# FPGA_config.net
KiCad netlist of a schematic drawn in Altium Designer
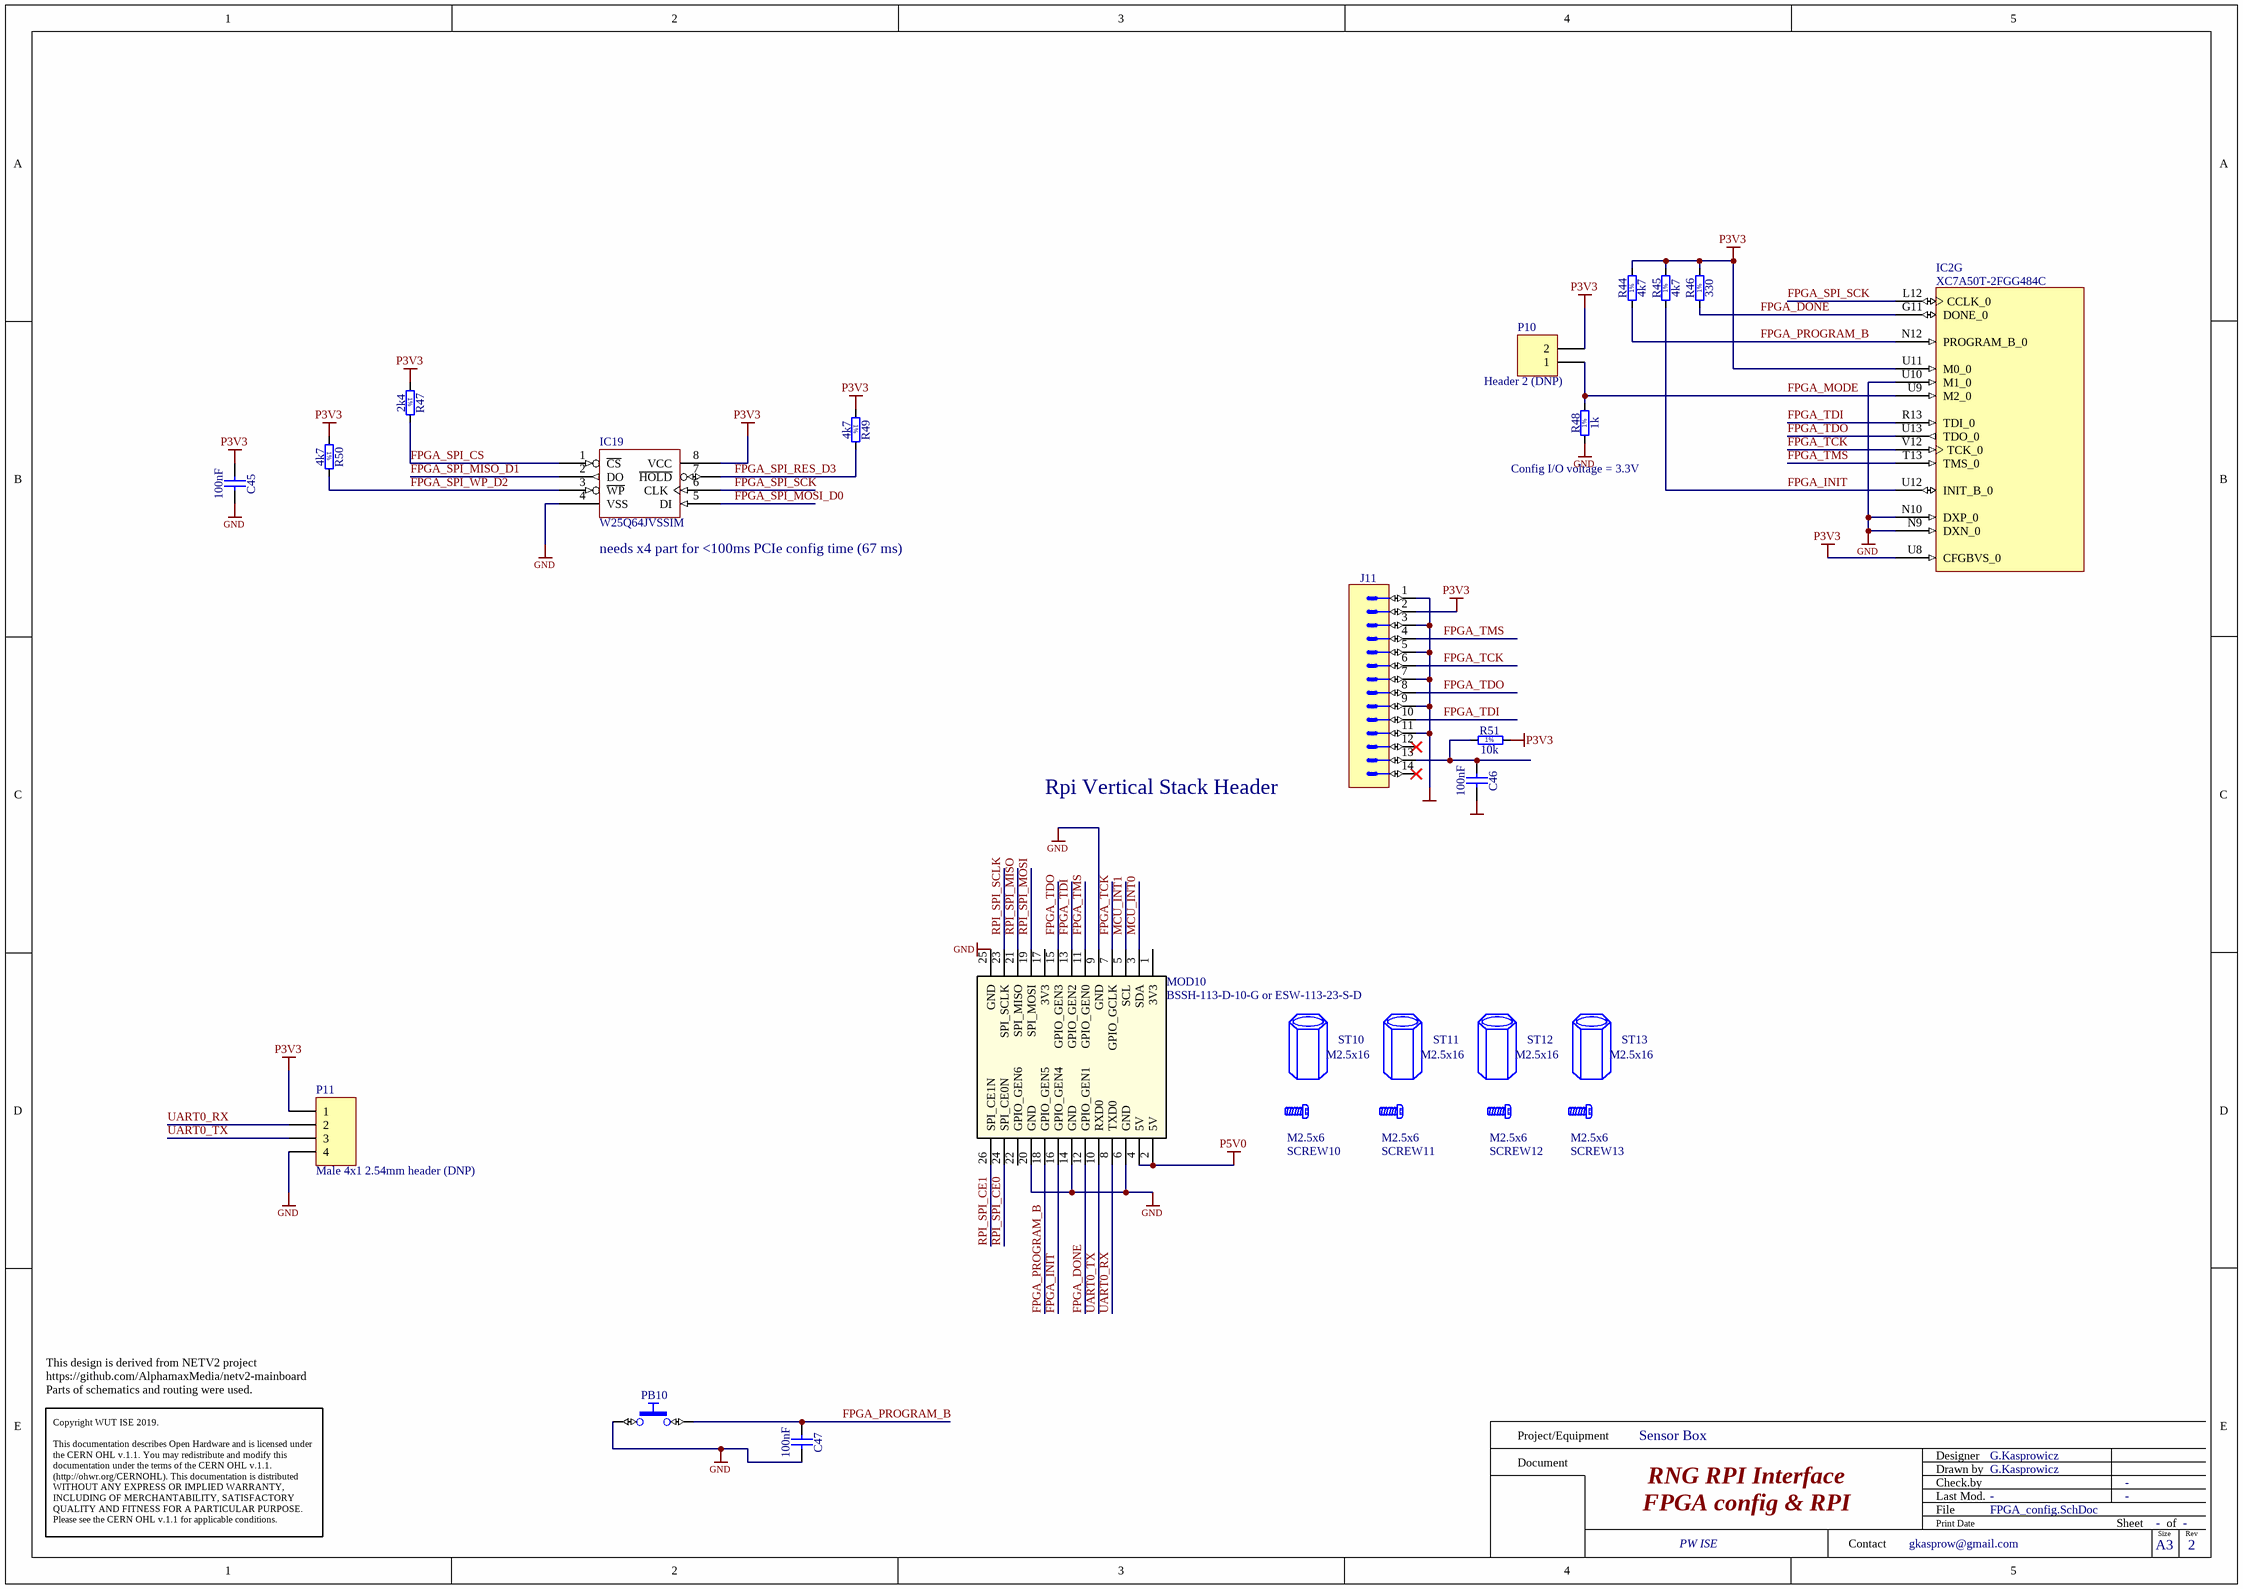
[diagram p0: FPGA_config.SchDoc]

(export (version "E")
  (design (tool "Eeschema 10.0.6"))
  (components
    (comp (ref "C45")
      (value "100nF")
      (footprint "CAPC0603X33N")
      (description "Non-polarised capacitor")
      (fields
        (field (name "PART NUMBER") "CC0201_100NF_6.3V_10%_X5R")
        (field (name "VOLTAGE") "6.3V")
        (field (name "AUTHOR") "CERN DEM JLC")
      )
      (libsource (lib "Capacitors") (part "Capacitor - non polarized"))
    )
    (comp (ref "C46")
      (value "100nF")
      (footprint "CAPC0603X33N")
      (description "Non-polarised capacitor")
      (fields
        (field (name "PART NUMBER") "CC0201_100NF_6.3V_10%_X5R")
        (field (name "VOLTAGE") "6.3V")
        (field (name "AUTHOR") "CERN DEM JLC")
      )
      (libsource (lib "Capacitors") (part "Capacitor - non polarized"))
    )
    (comp (ref "C47")
      (value "100nF")
      (footprint "CAPC0603X33N")
      (description "Non-polarised capacitor")
      (fields
        (field (name "PART NUMBER") "CC0201_100NF_6.3V_10%_X5R")
        (field (name "VOLTAGE") "6.3V")
        (field (name "AUTHOR") "CERN DEM JLC")
      )
      (libsource (lib "Capacitors") (part "Capacitor - non polarized"))
    )
    (comp (ref "IC2")
      (value "XC7A50T-2FGG484C")
      (footprint "BGA484C100P22X22_2300X2300X260")
      (fields (field (name "MANUFACTURER") "XILINX") (field (name "AUTHOR") "CERN DEM JMW"))
      (libsource (lib "ICs And Semiconductors") (part "XC7A50T-2FGG484C"))
    )
    (comp (ref "IC19")
      (value "W25Q64JVSSIM")
      (footprint "SOIC127P790X216-8N")
      (description "64Mbit SPI NOR FLASH")
      (libsource (lib "commonsch") (part "EN25P05-50GCP"))
    )
    (comp (ref "J11")
      (value "Milli-Grid™")
      (footprint "MOLEX_87832-1420")
      (description "Connector 14 Male")
      (fields
        (field (name "PART NUMBER") "MOLEX_87832-1420")
        (field (name "MANUFACTURER") "MOLEX")
        (field (name "AUTHOR") "CERN DEM JLC")
      )
      (libsource (lib "Connectors") (part "Connector 14 Male"))
    )
    (comp (ref "MOD10")
      (value "BSSH-113-D-10-G or ESW-113-23-S-D")
      (footprint "Raspberr Pi - 26")
      (description "Raspberry Pi - 26")
      (fields (field (name "MANUFACTURER") "Major League Electroncis"))
      (libsource (lib "Modules") (part "Raspberry Pi - 26"))
    )
    (comp (ref "P10")
      (value "Header 2 (DNP)")
      (footprint "HDR1X2")
      (description "Header, 2-Pin")
      (fields (field (name "MPN") "DNP") (field (name "PUBLISHER") "Altium Limited"))
      (libsource (lib "Miscellaneous Connectors") (part "Header 2"))
    )
    (comp (ref "P11")
      (value "Male 4x1 2.54mm header (DNP)")
      (footprint "HDR1X4")
      (description "Header, 4-Pin")
      (fields (field (name "MPN") "DNP") (field (name "PUBLISHER") "Altium Limited"))
      (libsource (lib "Miscellaneous Connectors") (part "Header 4"))
    )
    (comp (ref "PB10")
      (value "Push Button")
      (footprint "PB_TYCO_FSMSM")
      (description "Push-Button Switch SPDT")
      (fields
        (field (name "PART NUMBER") "PB_TYCO_FSMSM")
        (field (name "MANUFACTURER") "TYCO ELECTRONICS")
        (field (name "AUTHOR") "CERN DEM JLC")
      )
      (libsource (lib "Eletro-mechanical") (part "PB SPST 1NO-2NO"))
    )
    (comp (ref "R44")
      (value "4k7")
      (footprint "RESC1005X40N")
      (description "Resistor - 1%")
      (fields
        (field (name "PART NUMBER") "R0402_4K7_1%_0.0625W_100PPM")
        (field (name "POWER") "0.0625W")
        (field (name "AUTHOR") "CERN DEM JLC")
      )
      (libsource (lib "Resistors") (part "Resistor - 1%"))
    )
    (comp (ref "R45")
      (value "4k7")
      (footprint "RESC1005X40N")
      (description "Resistor - 1%")
      (fields
        (field (name "PART NUMBER") "R0402_4K7_1%_0.0625W_100PPM")
        (field (name "POWER") "0.0625W")
        (field (name "AUTHOR") "CERN DEM JLC")
      )
      (libsource (lib "Resistors") (part "Resistor - 1%"))
    )
    (comp (ref "R46")
      (value "330")
      (footprint "RESC1005X40N")
      (description "Resistor - 1%")
      (fields
        (field (name "PART NUMBER") "R0402_330R_1%_0.0625W_100PPM")
        (field (name "POWER") "0.0625W")
        (field (name "AUTHOR") "CERN DEM JLC")
      )
      (libsource (lib "Resistors") (part "Resistor - 1%"))
    )
    (comp (ref "R47")
      (value "2k4")
      (footprint "RESC1005X40N")
      (description "Resistor - 1%")
      (fields
        (field (name "PART NUMBER") "R0402_2K4_1%_0.0625W_100PPM")
        (field (name "POWER") "0.0625W")
        (field (name "AUTHOR") "CERN DEM JLC")
      )
      (libsource (lib "Resistors") (part "Resistor - 1%"))
    )
    (comp (ref "R48")
      (value "1k")
      (footprint "RESC1005X40N")
      (description "Resistor - 1%")
      (fields
        (field (name "PART NUMBER") "R0402_1K_1%_0.0625W_100PPM")
        (field (name "POWER") "0.0625W")
        (field (name "AUTHOR") "CERN DEM JLC")
      )
      (libsource (lib "Resistors") (part "Resistor - 1%"))
    )
    (comp (ref "R49")
      (value "4k7")
      (footprint "RESC1005X40N")
      (description "Resistor - 1%")
      (fields
        (field (name "PART NUMBER") "R0402_4K7_1%_0.0625W_100PPM")
        (field (name "POWER") "0.0625W")
        (field (name "AUTHOR") "CERN DEM JLC")
      )
      (libsource (lib "Resistors") (part "Resistor - 1%"))
    )
    (comp (ref "R50")
      (value "4k7")
      (footprint "RESC1005X40N")
      (description "Resistor - 1%")
      (fields
        (field (name "PART NUMBER") "R0402_4K7_1%_0.0625W_100PPM")
        (field (name "POWER") "0.0625W")
        (field (name "AUTHOR") "CERN DEM JLC")
      )
      (libsource (lib "Resistors") (part "Resistor - 1%"))
    )
    (comp (ref "R51")
      (value "10k")
      (footprint "RESC1005X40N")
      (description "Resistor - 1%")
      (fields
        (field (name "PART NUMBER") "R0402_10K_1%_0.0625W_100PPM")
        (field (name "POWER") "0.0625W")
        (field (name "AUTHOR") "CERN DEM JLC")
      )
      (libsource (lib "Resistors") (part "Resistor - 1%"))
    )
    (comp (ref "SCREW10")
      (value "M2.5x6")
      (footprint "BOSSARD_BN5687-3061597_v")
      (description "Screw")
      (fields
        (field (name "PART NUMBER") "BOSSARD_BN5687-3061597_v")
        (field (name "MANUFACTURER") "BOSSARD")
        (field (name "AUTHOR") "CERN DEM JLC")
      )
      (libsource (lib "Eletro-mechanical") (part "Screw"))
    )
    (comp (ref "SCREW11")
      (value "M2.5x6")
      (footprint "BOSSARD_BN5687-3061597_v")
      (description "Screw")
      (fields
        (field (name "PART NUMBER") "BOSSARD_BN5687-3061597_v")
        (field (name "MANUFACTURER") "BOSSARD")
        (field (name "AUTHOR") "CERN DEM JLC")
      )
      (libsource (lib "Eletro-mechanical") (part "Screw"))
    )
    (comp (ref "SCREW12")
      (value "M2.5x6")
      (footprint "BOSSARD_BN5687-3061597_v")
      (description "Screw")
      (fields
        (field (name "PART NUMBER") "BOSSARD_BN5687-3061597_v")
        (field (name "MANUFACTURER") "BOSSARD")
        (field (name "AUTHOR") "CERN DEM JLC")
      )
      (libsource (lib "Eletro-mechanical") (part "Screw"))
    )
    (comp (ref "SCREW13")
      (value "M2.5x6")
      (footprint "BOSSARD_BN5687-3061597_v")
      (description "Screw")
      (fields
        (field (name "PART NUMBER") "BOSSARD_BN5687-3061597_v")
        (field (name "MANUFACTURER") "BOSSARD")
        (field (name "AUTHOR") "CERN DEM JLC")
      )
      (libsource (lib "Eletro-mechanical") (part "Screw"))
    )
    (comp (ref "ST10")
      (value "M2.5x16")
      (footprint "WURTH_970160155")
      (description "M2.5x16 plastic standoff")
      (fields
        (field (name "PART NUMBER") "WURTH_970160155")
        (field (name "MANUFACTURER") "WURTH")
        (field (name "AUTHOR") "GK")
      )
      (libsource (lib "Mechanical") (part "MECH_Standoff_M2.5x16"))
    )
    (comp (ref "ST11")
      (value "M2.5x16")
      (footprint "WURTH_970160155")
      (description "M2.5x16 plastic standoff")
      (fields
        (field (name "PART NUMBER") "WURTH_970160155")
        (field (name "MANUFACTURER") "WURTH")
        (field (name "AUTHOR") "GK")
      )
      (libsource (lib "Mechanical") (part "MECH_Standoff_M2.5x16"))
    )
    (comp (ref "ST12")
      (value "M2.5x16")
      (footprint "WURTH_970160155")
      (description "M2.5x16 plastic standoff")
      (fields
        (field (name "PART NUMBER") "WURTH_970160155")
        (field (name "MANUFACTURER") "WURTH")
        (field (name "AUTHOR") "GK")
      )
      (libsource (lib "Mechanical") (part "MECH_Standoff_M2.5x16"))
    )
    (comp (ref "ST13")
      (value "M2.5x16")
      (footprint "WURTH_970160155")
      (description "M2.5x16 plastic standoff")
      (fields
        (field (name "PART NUMBER") "WURTH_970160155")
        (field (name "MANUFACTURER") "WURTH")
        (field (name "AUTHOR") "GK")
      )
      (libsource (lib "Mechanical") (part "MECH_Standoff_M2.5x16"))
    )
  )
  (nets
    (net (code "1") (name "/FPGA_DONE") (class "Default")
      (node (ref "IC2") (pin "G11") (pinfunction "DONE_0_G11") (pintype "bidirectional"))
      (node (ref "MOD10") (pin "12") (pinfunction "GPIO_GEN1_12") (pintype "passive"))
      (node (ref "R46") (pin "1") (pinfunction "1_1") (pintype "passive"))
    )
    (net (code "2") (name "/FPGA_INIT") (class "Default")
      (node (ref "IC2") (pin "U12") (pinfunction "INIT_B_0_U12") (pintype "bidirectional"))
      (node (ref "MOD10") (pin "16") (pinfunction "GPIO_GEN4_16") (pintype "passive"))
      (node (ref "R45") (pin "1") (pinfunction "1_1") (pintype "passive"))
    )
    (net (code "3") (name "/FPGA_MODE") (class "Default")
      (node (ref "IC2") (pin "U9") (pinfunction "M2_0_U9") (pintype "input"))
      (node (ref "P10") (pin "1") (pinfunction "1_1") (pintype "passive"))
      (node (ref "R48") (pin "2") (pinfunction "2_2") (pintype "passive"))
    )
    (net (code "4") (name "/FPGA_PROGRAM_B") (class "Default")
      (node (ref "C47") (pin "1") (pinfunction "1_1") (pintype "passive"))
      (node (ref "IC2") (pin "N12") (pinfunction "PROGRAM_B_0_N12") (pintype "input"))
      (node (ref "MOD10") (pin "18") (pinfunction "GPIO_GEN5_18") (pintype "passive"))
      (node (ref "PB10") (pin "2") (pinfunction "2_2") (pintype "bidirectional"))
      (node (ref "R44") (pin "1") (pinfunction "1_1") (pintype "passive"))
    )
    (net (code "5") (name "/FPGA_SPI_CS") (class "Default")
      (node (ref "IC19") (pin "1") (pinfunction "~{CS}_1") (pintype "input"))
      (node (ref "R47") (pin "2") (pinfunction "2_2") (pintype "passive"))
    )
    (net (code "6") (name "/FPGA_SPI_MISO_D1") (class "Default")
      (node (ref "IC19") (pin "2") (pinfunction "DO_2") (pintype "output"))
    )
    (net (code "7") (name "/FPGA_SPI_MOSI_D0") (class "Default")
      (node (ref "IC19") (pin "5") (pinfunction "DI_5") (pintype "input"))
    )
    (net (code "8") (name "/FPGA_SPI_RES_D3") (class "Default")
      (node (ref "IC19") (pin "7") (pinfunction "~{HOLD}_7") (pintype "bidirectional"))
      (node (ref "R49") (pin "2") (pinfunction "2_2") (pintype "passive"))
    )
    (net (code "9") (name "/FPGA_SPI_SCK") (class "Default")
      (node (ref "IC19") (pin "6") (pinfunction "CLK_6") (pintype "input"))
      (node (ref "IC2") (pin "L12") (pinfunction "CCLK_0_L12") (pintype "bidirectional"))
    )
    (net (code "10") (name "/FPGA_SPI_WP_D2") (class "Default")
      (node (ref "IC19") (pin "3") (pinfunction "~{WP}_3") (pintype "input"))
      (node (ref "R50") (pin "2") (pinfunction "2_2") (pintype "passive"))
    )
    (net (code "11") (name "/FPGA_TCK") (class "Default")
      (node (ref "IC2") (pin "V12") (pinfunction "TCK_0_V12") (pintype "input"))
      (node (ref "J11") (pin "6") (pinfunction "6_6") (pintype "bidirectional"))
      (node (ref "MOD10") (pin "7") (pinfunction "GPIO_GCLK_7") (pintype "passive"))
    )
    (net (code "12") (name "/FPGA_TDI") (class "Default")
      (node (ref "IC2") (pin "R13") (pinfunction "TDI_0_R13") (pintype "input"))
      (node (ref "J11") (pin "10") (pinfunction "10_10") (pintype "bidirectional"))
      (node (ref "MOD10") (pin "13") (pinfunction "GPIO_GEN2_13") (pintype "passive"))
    )
    (net (code "13") (name "/FPGA_TDO") (class "Default")
      (node (ref "IC2") (pin "U13") (pinfunction "TDO_0_U13") (pintype "output"))
      (node (ref "J11") (pin "8") (pinfunction "8_8") (pintype "bidirectional"))
      (node (ref "MOD10") (pin "15") (pinfunction "GPIO_GEN3_15") (pintype "passive"))
    )
    (net (code "14") (name "/FPGA_TMS") (class "Default")
      (node (ref "IC2") (pin "T13") (pinfunction "TMS_0_T13") (pintype "input"))
      (node (ref "J11") (pin "4") (pinfunction "4_4") (pintype "bidirectional"))
      (node (ref "MOD10") (pin "11") (pinfunction "GPIO_GEN0_11") (pintype "passive"))
    )
    (net (code "15") (name "/MCU_INT0") (class "Default")
      (node (ref "MOD10") (pin "3") (pinfunction "SDA_3") (pintype "passive"))
    )
    (net (code "16") (name "/MCU_INT1") (class "Default")
      (node (ref "MOD10") (pin "5") (pinfunction "SCL_5") (pintype "passive"))
    )
    (net (code "17") (name "/RPI_SPI_CE0") (class "Default")
      (node (ref "MOD10") (pin "24") (pinfunction "SPI_CE0N_24") (pintype "passive"))
    )
    (net (code "18") (name "/RPI_SPI_CE1") (class "Default")
      (node (ref "MOD10") (pin "26") (pinfunction "SPI_CE1N_26") (pintype "passive"))
    )
    (net (code "19") (name "/RPI_SPI_MISO") (class "Default")
      (node (ref "MOD10") (pin "21") (pinfunction "SPI_MISO_21") (pintype "passive"))
    )
    (net (code "20") (name "/RPI_SPI_MOSI") (class "Default")
      (node (ref "MOD10") (pin "19") (pinfunction "SPI_MOSI_19") (pintype "passive"))
    )
    (net (code "21") (name "/RPI_SPI_SCLK") (class "Default")
      (node (ref "MOD10") (pin "23") (pinfunction "SPI_SCLK_23") (pintype "passive"))
    )
    (net (code "22") (name "/UART0_RX") (class "Default")
      (node (ref "MOD10") (pin "8") (pinfunction "TXD0_8") (pintype "passive"))
      (node (ref "P11") (pin "2") (pinfunction "2_2") (pintype "passive"))
    )
    (net (code "23") (name "/UART0_TX") (class "Default")
      (node (ref "MOD10") (pin "10") (pinfunction "RXD0_10") (pintype "passive"))
      (node (ref "P11") (pin "3") (pinfunction "3_3") (pintype "passive"))
    )
    (net (code "24") (name "GND") (class "Default")
      (node (ref "C45") (pin "2") (pinfunction "2_2") (pintype "passive"))
      (node (ref "C46") (pin "2") (pinfunction "2_2") (pintype "passive"))
      (node (ref "C47") (pin "2") (pinfunction "2_2") (pintype "passive"))
      (node (ref "IC19") (pin "4") (pinfunction "VSS_4") (pintype "power_in"))
      (node (ref "IC2") (pin "N10") (pinfunction "DXP_0_N10") (pintype "input"))
      (node (ref "IC2") (pin "N9") (pinfunction "DXN_0_N9") (pintype "input"))
      (node (ref "IC2") (pin "U10") (pinfunction "M1_0_U10") (pintype "input"))
      (node (ref "J11") (pin "1") (pinfunction "1_1") (pintype "bidirectional"))
      (node (ref "J11") (pin "11") (pinfunction "11_11") (pintype "bidirectional"))
      (node (ref "J11") (pin "3") (pinfunction "3_3") (pintype "bidirectional"))
      (node (ref "J11") (pin "5") (pinfunction "5_5") (pintype "bidirectional"))
      (node (ref "J11") (pin "7") (pinfunction "7_7") (pintype "bidirectional"))
      (node (ref "J11") (pin "9") (pinfunction "9_9") (pintype "bidirectional"))
      (node (ref "MOD10") (pin "14") (pinfunction "GND_14") (pintype "passive"))
      (node (ref "MOD10") (pin "20") (pinfunction "GND_20") (pintype "passive"))
      (node (ref "MOD10") (pin "25") (pinfunction "GND_25") (pintype "passive"))
      (node (ref "MOD10") (pin "6") (pinfunction "GND_6") (pintype "passive"))
      (node (ref "MOD10") (pin "9") (pinfunction "GND_9") (pintype "passive"))
      (node (ref "P11") (pin "4") (pinfunction "4_4") (pintype "passive"))
      (node (ref "PB10") (pin "1") (pinfunction "1_1") (pintype "bidirectional"))
      (node (ref "R48") (pin "1") (pinfunction "1_1") (pintype "passive"))
    )
    (net (code "25") (name "Net-(C46-Pad1)") (class "Default")
      (node (ref "C46") (pin "1") (pinfunction "1_1") (pintype "passive"))
      (node (ref "J11") (pin "13") (pinfunction "13_13") (pintype "bidirectional"))
      (node (ref "R51") (pin "1") (pinfunction "1_1") (pintype "passive"))
    )
    (net (code "26") (name "P3V3") (class "Default")
      (node (ref "C45") (pin "1") (pinfunction "1_1") (pintype "passive"))
      (node (ref "IC19") (pin "8") (pinfunction "VCC_8") (pintype "power_in"))
      (node (ref "IC2") (pin "U11") (pinfunction "M0_0_U11") (pintype "input"))
      (node (ref "IC2") (pin "U8") (pinfunction "CFGBVS_0_U8") (pintype "input"))
      (node (ref "J11") (pin "2") (pinfunction "2_2") (pintype "bidirectional"))
      (node (ref "P10") (pin "2") (pinfunction "2_2") (pintype "passive"))
      (node (ref "P11") (pin "1") (pinfunction "1_1") (pintype "passive"))
      (node (ref "R44") (pin "2") (pinfunction "2_2") (pintype "passive"))
      (node (ref "R45") (pin "2") (pinfunction "2_2") (pintype "passive"))
      (node (ref "R46") (pin "2") (pinfunction "2_2") (pintype "passive"))
      (node (ref "R47") (pin "1") (pinfunction "1_1") (pintype "passive"))
      (node (ref "R49") (pin "1") (pinfunction "1_1") (pintype "passive"))
      (node (ref "R50") (pin "1") (pinfunction "1_1") (pintype "passive"))
      (node (ref "R51") (pin "2") (pinfunction "2_2") (pintype "passive"))
    )
    (net (code "27") (name "P5V0") (class "Default")
      (node (ref "MOD10") (pin "2") (pinfunction "5V_2") (pintype "passive"))
      (node (ref "MOD10") (pin "4") (pinfunction "5V_4") (pintype "passive"))
    )
    (net (code "28") (name "unconnected-(J11-Pad12)") (class "Default")
      (node (ref "J11") (pin "12") (pinfunction "12_12") (pintype "bidirectional+no_connect"))
    )
    (net (code "29") (name "unconnected-(J11-Pad14)") (class "Default")
      (node (ref "J11") (pin "14") (pinfunction "14_14") (pintype "bidirectional+no_connect"))
    )
    (net (code "30") (name "unconnected-(MOD10-3V3-Pad1)") (class "Default")
      (node (ref "MOD10") (pin "1") (pinfunction "3V3_1") (pintype "passive"))
    )
    (net (code "31") (name "unconnected-(MOD10-3V3-Pad17)") (class "Default")
      (node (ref "MOD10") (pin "17") (pinfunction "3V3_17") (pintype "passive"))
    )
    (net (code "32") (name "unconnected-(MOD10-GPIO_GEN6-Pad22)") (class "Default")
      (node (ref "MOD10") (pin "22") (pinfunction "GPIO_GEN6_22") (pintype "passive"))
    )
  )
)
